# BlinkyLight.net
KiCad netlist of a schematic drawn in EAGLE
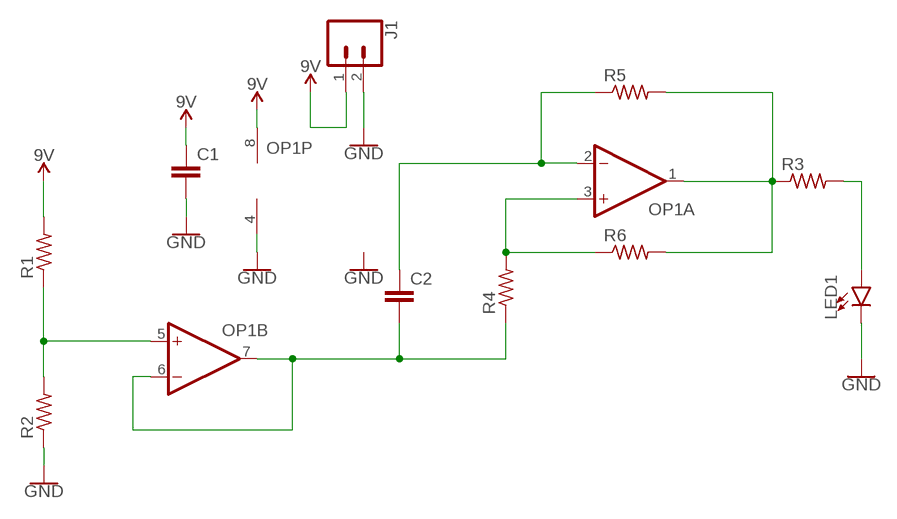
[diagram p0: schematic, sheet 1]

(export (version "E")
  (design (tool "Eeschema 10.0.6"))
  (components
    (comp (ref "C1")
      (value "CAPACITOR0603")
      (footprint "eagle-import:C0603")
      (libsource (lib "eagle-import") (part "CAPACITOR0603"))
    )
    (comp (ref "C2")
      (value "CAPACITOR0603")
      (footprint "eagle-import:C0603")
      (libsource (lib "eagle-import") (part "CAPACITOR0603"))
    )
    (comp (ref "J1")
      (value "CONN_02")
      (footprint "eagle-import:1X02")
      (libsource (lib "eagle-import") (part "CONN_02"))
    )
    (comp (ref "LED1")
      (value "LED5MM")
      (footprint "eagle-import:LED_5MM")
      (libsource (lib "eagle-import") (part "LED5MM"))
    )
    (comp (ref "OP1")
      (value "OP-DUALR")
      (footprint "eagle-import:SO8")
      (fields (field (name "MPN") "AD8607ARMZ-R2"))
      (libsource (lib "eagle-import") (part "OP-DUALR"))
    )
    (comp (ref "R1")
      (value "RESISTOR0603")
      (footprint "eagle-import:R0603")
      (libsource (lib "eagle-import") (part "RESISTOR0603"))
    )
    (comp (ref "R2")
      (value "RESISTOR0603")
      (footprint "eagle-import:R0603")
      (libsource (lib "eagle-import") (part "RESISTOR0603"))
    )
    (comp (ref "R3")
      (value "RESISTOR0603")
      (footprint "eagle-import:R0603")
      (libsource (lib "eagle-import") (part "RESISTOR0603"))
    )
    (comp (ref "R4")
      (value "RESISTOR0603")
      (footprint "eagle-import:R0603")
      (libsource (lib "eagle-import") (part "RESISTOR0603"))
    )
    (comp (ref "R5")
      (value "RESISTOR0603")
      (footprint "eagle-import:R0603")
      (libsource (lib "eagle-import") (part "RESISTOR0603"))
    )
    (comp (ref "R6")
      (value "RESISTOR0603")
      (footprint "eagle-import:R0603")
      (libsource (lib "eagle-import") (part "RESISTOR0603"))
    )
  )
  (nets
    (net (code "1") (name "9V") (class "Default")
      (node (ref "C1") (pin "1") (pinfunction "1_1") (pintype "passive"))
      (node (ref "J1") (pin "1") (pinfunction "1_1") (pintype "passive"))
      (node (ref "OP1") (pin "8") (pinfunction "V+_8") (pintype "power_in"))
      (node (ref "R1") (pin "2") (pinfunction "2_2") (pintype "passive"))
    )
    (net (code "2") (name "GND") (class "Default")
      (node (ref "C1") (pin "2") (pinfunction "2_2") (pintype "passive"))
      (node (ref "J1") (pin "2") (pinfunction "2_2") (pintype "passive"))
      (node (ref "LED1") (pin "K") (pinfunction "C_K") (pintype "passive"))
      (node (ref "OP1") (pin "4") (pinfunction "V-_4") (pintype "power_in"))
      (node (ref "R2") (pin "1") (pinfunction "1_1") (pintype "passive"))
    )
    (net (code "3") (name "Net-(LED1-PadA)") (class "Default")
      (node (ref "LED1") (pin "A") (pinfunction "A_A") (pintype "passive"))
      (node (ref "R3") (pin "2") (pinfunction "2_2") (pintype "passive"))
    )
    (net (code "4") (name "Net-(OP1A-+IN)") (class "Default")
      (node (ref "OP1") (pin "3") (pinfunction "+IN_3") (pintype "input"))
      (node (ref "R4") (pin "2") (pinfunction "2_2") (pintype "passive"))
      (node (ref "R6") (pin "1") (pinfunction "1_1") (pintype "passive"))
    )
    (net (code "5") (name "Net-(OP1A--IN)") (class "Default")
      (node (ref "C2") (pin "1") (pinfunction "1_1") (pintype "passive"))
      (node (ref "OP1") (pin "2") (pinfunction "-IN_2") (pintype "input"))
      (node (ref "R5") (pin "1") (pinfunction "1_1") (pintype "passive"))
    )
    (net (code "6") (name "Net-(OP1A-OUT)") (class "Default")
      (node (ref "OP1") (pin "1") (pinfunction "OUT_1") (pintype "output"))
      (node (ref "R3") (pin "1") (pinfunction "1_1") (pintype "passive"))
      (node (ref "R5") (pin "2") (pinfunction "2_2") (pintype "passive"))
      (node (ref "R6") (pin "2") (pinfunction "2_2") (pintype "passive"))
    )
    (net (code "7") (name "Net-(OP1B-+IN)") (class "Default")
      (node (ref "OP1") (pin "5") (pinfunction "+IN_5") (pintype "input"))
      (node (ref "R1") (pin "1") (pinfunction "1_1") (pintype "passive"))
      (node (ref "R2") (pin "2") (pinfunction "2_2") (pintype "passive"))
    )
    (net (code "8") (name "Net-(OP1B--IN)") (class "Default")
      (node (ref "C2") (pin "2") (pinfunction "2_2") (pintype "passive"))
      (node (ref "OP1") (pin "6") (pinfunction "-IN_6") (pintype "input"))
      (node (ref "OP1") (pin "7") (pinfunction "OUT_7") (pintype "output"))
      (node (ref "R4") (pin "1") (pinfunction "1_1") (pintype "passive"))
    )
  )
)
